# IC4KL_due_cont.net
KiCad netlist of a schematic drawn in EAGLE
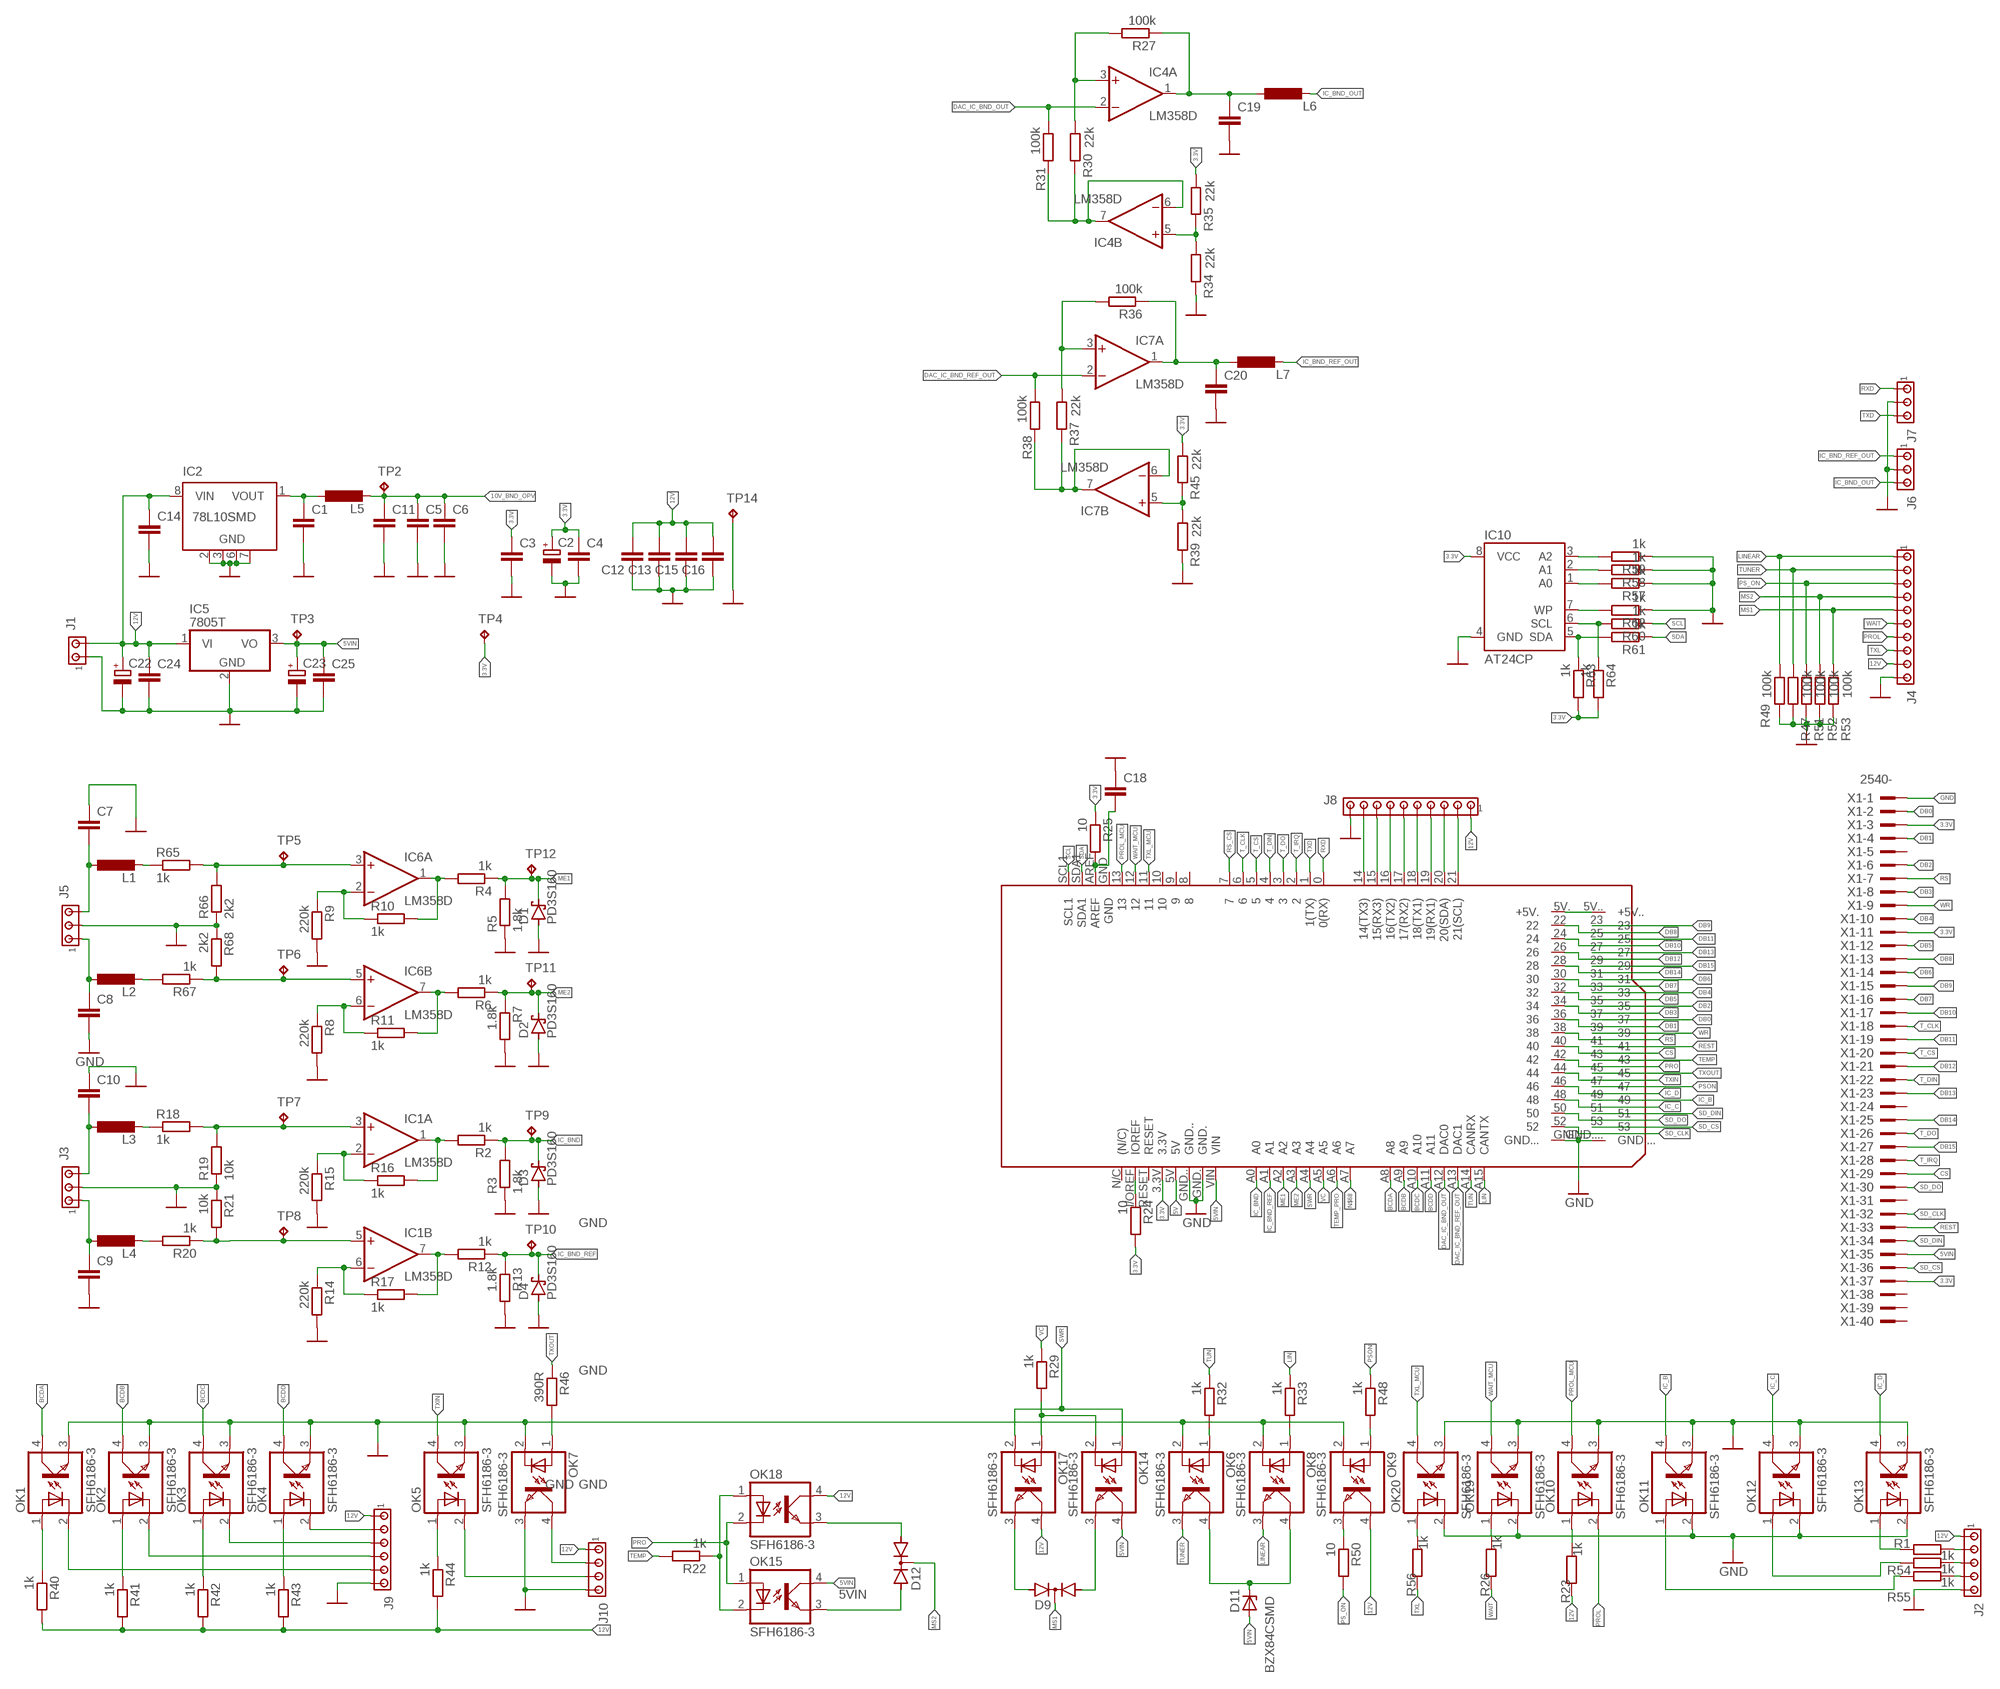
[diagram p0: schematic, sheet 1]

(export (version "E")
  (design (tool "Eeschema 10.0.6"))
  (components
    (comp (ref "C1")
      (value "1u")
      (footprint "eagle-import:C0805K")
      (libsource (lib "eagle-import") (part "C-EUC0805K"))
    )
    (comp (ref "C2")
      (value "CPOL-EU085CS-1AW")
      (footprint "eagle-import:085CS_1AW")
      (libsource (lib "eagle-import") (part "CPOL-EU085CS-1AW"))
    )
    (comp (ref "C3")
      (value "C-EUC0805K")
      (footprint "eagle-import:C0805K")
      (libsource (lib "eagle-import") (part "C-EUC0805K"))
    )
    (comp (ref "C4")
      (value "C-EUC0805K")
      (footprint "eagle-import:C0805K")
      (libsource (lib "eagle-import") (part "C-EUC0805K"))
    )
    (comp (ref "C5")
      (value "1u")
      (footprint "eagle-import:C0805K")
      (libsource (lib "eagle-import") (part "C-EUC0805K"))
    )
    (comp (ref "C6")
      (value "1u")
      (footprint "eagle-import:C0805K")
      (libsource (lib "eagle-import") (part "C-EUC0805K"))
    )
    (comp (ref "C7")
      (value "100n")
      (footprint "eagle-import:C0805K")
      (libsource (lib "eagle-import") (part "C-EUC0805K"))
    )
    (comp (ref "C8")
      (value "100n")
      (footprint "eagle-import:C0805K")
      (libsource (lib "eagle-import") (part "C-EUC0805K"))
    )
    (comp (ref "C9")
      (value "C-EUC0805K")
      (footprint "eagle-import:C0805K")
      (libsource (lib "eagle-import") (part "C-EUC0805K"))
    )
    (comp (ref "C10")
      (value "C-EUC0805K")
      (footprint "eagle-import:C0805K")
      (libsource (lib "eagle-import") (part "C-EUC0805K"))
    )
    (comp (ref "C11")
      (value "1u")
      (footprint "eagle-import:C0805K")
      (libsource (lib "eagle-import") (part "C-EUC0805K"))
    )
    (comp (ref "C12")
      (value "100n")
      (footprint "eagle-import:C0805K")
      (libsource (lib "eagle-import") (part "C-EUC0805K"))
    )
    (comp (ref "C13")
      (value "100n")
      (footprint "eagle-import:C0805K")
      (libsource (lib "eagle-import") (part "C-EUC0805K"))
    )
    (comp (ref "C14")
      (value "1u")
      (footprint "eagle-import:C0805K")
      (libsource (lib "eagle-import") (part "C-EUC0805K"))
    )
    (comp (ref "C15")
      (value "100n")
      (footprint "eagle-import:C0805K")
      (libsource (lib "eagle-import") (part "C-EUC0805K"))
    )
    (comp (ref "C16")
      (value "100n")
      (footprint "eagle-import:C0805K")
      (libsource (lib "eagle-import") (part "C-EUC0805K"))
    )
    (comp (ref "C18")
      (value "C-EUC0805K")
      (footprint "eagle-import:C0805K")
      (libsource (lib "eagle-import") (part "C-EUC0805K"))
    )
    (comp (ref "C19")
      (value "C-EUC0805K")
      (footprint "eagle-import:C0805K")
      (libsource (lib "eagle-import") (part "C-EUC0805K"))
    )
    (comp (ref "C20")
      (value "C-EUC0805K")
      (footprint "eagle-import:C0805K")
      (libsource (lib "eagle-import") (part "C-EUC0805K"))
    )
    (comp (ref "C22")
      (value "CPOL-EU150CLZ-1010")
      (footprint "eagle-import:150CLZ-1010")
      (libsource (lib "eagle-import") (part "CPOL-EU150CLZ-1010"))
    )
    (comp (ref "C23")
      (value "CPOL-EU150CLZ-1010")
      (footprint "eagle-import:150CLZ-1010")
      (libsource (lib "eagle-import") (part "CPOL-EU150CLZ-1010"))
    )
    (comp (ref "C24")
      (value "C-EUC0805K")
      (footprint "eagle-import:C0805K")
      (libsource (lib "eagle-import") (part "C-EUC0805K"))
    )
    (comp (ref "C25")
      (value "C-EUC0805K")
      (footprint "eagle-import:C0805K")
      (libsource (lib "eagle-import") (part "C-EUC0805K"))
    )
    (comp (ref "D1")
      (value "PD3S160")
      (footprint "eagle-import:POWERDI323")
      (libsource (lib "eagle-import") (part "PD3S160"))
    )
    (comp (ref "D2")
      (value "PD3S160")
      (footprint "eagle-import:POWERDI323")
      (libsource (lib "eagle-import") (part "PD3S160"))
    )
    (comp (ref "D3")
      (value "PD3S160")
      (footprint "eagle-import:POWERDI323")
      (libsource (lib "eagle-import") (part "PD3S160"))
    )
    (comp (ref "D4")
      (value "PD3S160")
      (footprint "eagle-import:POWERDI323")
      (libsource (lib "eagle-import") (part "PD3S160"))
    )
    (comp (ref "D9")
      (value "DIODE-2AC|CASOT23")
      (footprint "eagle-import:SOT23")
      (libsource (lib "eagle-import") (part "DIODE-2AC|CASOT23"))
    )
    (comp (ref "D11")
      (value "BZX84CSMD")
      (footprint "eagle-import:TO236")
      (libsource (lib "eagle-import") (part "BZX84CSMD"))
    )
    (comp (ref "D12")
      (value "DIODE-2AC|CASOT23")
      (footprint "eagle-import:SOT23")
      (libsource (lib "eagle-import") (part "DIODE-2AC|CASOT23"))
    )
    (comp (ref "IC1")
      (value "LM358D")
      (footprint "eagle-import:SO08")
      (libsource (lib "eagle-import") (part "LM358D"))
    )
    (comp (ref "IC2")
      (value "78L10SMD")
      (footprint "eagle-import:SO08")
      (libsource (lib "eagle-import") (part "78LSMD08"))
    )
    (comp (ref "IC4")
      (value "LM358D")
      (footprint "eagle-import:SO08")
      (libsource (lib "eagle-import") (part "linear_262_LM358D"))
    )
    (comp (ref "IC5")
      (value "7805T")
      (footprint "eagle-import:TO220H")
      (libsource (lib "eagle-import") (part "78T05"))
    )
    (comp (ref "IC6")
      (value "LM358D")
      (footprint "eagle-import:SO08")
      (libsource (lib "eagle-import") (part "LM358D"))
    )
    (comp (ref "IC7")
      (value "LM358D")
      (footprint "eagle-import:SO08")
      (libsource (lib "eagle-import") (part "linear_262_LM358D"))
    )
    (comp (ref "IC10")
      (value "AT24CP")
      (footprint "eagle-import:DIL08")
      (fields (field (name "MPN") "AT24C1024BW-SH-B"))
      (libsource (lib "eagle-import") (part "AT24CP"))
    )
    (comp (ref "J1")
      (value "MTA02-100")
      (footprint "eagle-import:10X02MTA")
      (libsource (lib "eagle-import") (part "MTA02-100"))
    )
    (comp (ref "J2")
      (value "MTA05-100")
      (footprint "eagle-import:10X05MTA")
      (libsource (lib "eagle-import") (part "MTA05-100"))
    )
    (comp (ref "J3")
      (value "MTA03-100")
      (footprint "eagle-import:10X03MTA")
      (libsource (lib "eagle-import") (part "MTA03-100"))
    )
    (comp (ref "J4")
      (value "MTA10-100")
      (footprint "eagle-import:10X10MTA")
      (libsource (lib "eagle-import") (part "MTA10-100"))
    )
    (comp (ref "J5")
      (value "MTA03-100")
      (footprint "eagle-import:10X03MTA")
      (libsource (lib "eagle-import") (part "MTA03-100"))
    )
    (comp (ref "J6")
      (value "MTA03-100")
      (footprint "eagle-import:10X03MTA")
      (libsource (lib "eagle-import") (part "MTA03-100"))
    )
    (comp (ref "J7")
      (value "MTA03-100")
      (footprint "eagle-import:10X03MTA")
      (libsource (lib "eagle-import") (part "MTA03-100"))
    )
    (comp (ref "J8")
      (value "MTA10-100")
      (footprint "eagle-import:10X10MTA")
      (libsource (lib "eagle-import") (part "MTA10-100"))
    )
    (comp (ref "J9")
      (value "MTA06-100")
      (footprint "eagle-import:10X06MTA")
      (libsource (lib "eagle-import") (part "MTA06-100"))
    )
    (comp (ref "J10")
      (value "MTA04-100")
      (footprint "eagle-import:10X04MTA")
      (libsource (lib "eagle-import") (part "MTA04-100"))
    )
    (comp (ref "L1")
      (value "L-EUL2012C")
      (footprint "eagle-import:L2012C")
      (libsource (lib "eagle-import") (part "L-EUL2012C"))
    )
    (comp (ref "L2")
      (value "L-EUL2012C")
      (footprint "eagle-import:L2012C")
      (libsource (lib "eagle-import") (part "L-EUL2012C"))
    )
    (comp (ref "L3")
      (value "L-EUL2012C")
      (footprint "eagle-import:L2012C")
      (libsource (lib "eagle-import") (part "L-EUL2012C"))
    )
    (comp (ref "L4")
      (value "L-EUL2012C")
      (footprint "eagle-import:L2012C")
      (libsource (lib "eagle-import") (part "L-EUL2012C"))
    )
    (comp (ref "L5")
      (value "L-EUL2012C")
      (footprint "eagle-import:L2012C")
      (libsource (lib "eagle-import") (part "L-EUL2012C"))
    )
    (comp (ref "L6")
      (value "L-EUL2012C")
      (footprint "eagle-import:L2012C")
      (libsource (lib "eagle-import") (part "L-EUL2012C"))
    )
    (comp (ref "L7")
      (value "L-EUL2012C")
      (footprint "eagle-import:L2012C")
      (libsource (lib "eagle-import") (part "L-EUL2012C"))
    )
    (comp (ref "OK1")
      (value "SFH6186-3")
      (footprint "eagle-import:SMD4")
      (fields (field (name "MF") "VISHAY/TELEFUNKEN"))
      (libsource (lib "eagle-import") (part "SFH618?6-3"))
    )
    (comp (ref "OK2")
      (value "SFH6186-3")
      (footprint "eagle-import:SMD4")
      (fields (field (name "MF") "VISHAY/TELEFUNKEN"))
      (libsource (lib "eagle-import") (part "SFH618?6-3"))
    )
    (comp (ref "OK3")
      (value "SFH6186-3")
      (footprint "eagle-import:SMD4")
      (fields (field (name "MF") "VISHAY/TELEFUNKEN"))
      (libsource (lib "eagle-import") (part "SFH618?6-3"))
    )
    (comp (ref "OK4")
      (value "SFH6186-3")
      (footprint "eagle-import:SMD4")
      (fields (field (name "MF") "VISHAY/TELEFUNKEN"))
      (libsource (lib "eagle-import") (part "SFH618?6-3"))
    )
    (comp (ref "OK5")
      (value "SFH6186-3")
      (footprint "eagle-import:SMD4")
      (fields (field (name "MF") "VISHAY/TELEFUNKEN"))
      (libsource (lib "eagle-import") (part "SFH618?6-3"))
    )
    (comp (ref "OK6")
      (value "SFH6186-3")
      (footprint "eagle-import:SMD4")
      (fields (field (name "MF") "VISHAY/TELEFUNKEN"))
      (libsource (lib "eagle-import") (part "SFH618?6-3"))
    )
    (comp (ref "OK7")
      (value "SFH6186-3")
      (footprint "eagle-import:SMD4")
      (fields (field (name "MF") "VISHAY/TELEFUNKEN"))
      (libsource (lib "eagle-import") (part "SFH618?6-3"))
    )
    (comp (ref "OK8")
      (value "SFH6186-3")
      (footprint "eagle-import:SMD4")
      (fields (field (name "MF") "VISHAY/TELEFUNKEN"))
      (libsource (lib "eagle-import") (part "SFH618?6-3"))
    )
    (comp (ref "OK9")
      (value "SFH6186-3")
      (footprint "eagle-import:SMD4")
      (fields (field (name "MF") "VISHAY/TELEFUNKEN"))
      (libsource (lib "eagle-import") (part "SFH618?6-3"))
    )
    (comp (ref "OK10")
      (value "SFH6186-3")
      (footprint "eagle-import:SMD4")
      (fields (field (name "MF") "VISHAY/TELEFUNKEN"))
      (libsource (lib "eagle-import") (part "SFH618?6-3"))
    )
    (comp (ref "OK11")
      (value "SFH6186-3")
      (footprint "eagle-import:SMD4")
      (fields (field (name "MF") "VISHAY/TELEFUNKEN"))
      (libsource (lib "eagle-import") (part "SFH618?6-3"))
    )
    (comp (ref "OK12")
      (value "SFH6186-3")
      (footprint "eagle-import:SMD4")
      (fields (field (name "MF") "VISHAY/TELEFUNKEN"))
      (libsource (lib "eagle-import") (part "SFH618?6-3"))
    )
    (comp (ref "OK13")
      (value "SFH6186-3")
      (footprint "eagle-import:SMD4")
      (fields (field (name "MF") "VISHAY/TELEFUNKEN"))
      (libsource (lib "eagle-import") (part "SFH618?6-3"))
    )
    (comp (ref "OK14")
      (value "SFH6186-3")
      (footprint "eagle-import:SMD4")
      (fields (field (name "MF") "VISHAY/TELEFUNKEN"))
      (libsource (lib "eagle-import") (part "SFH618?6-3"))
    )
    (comp (ref "OK15")
      (value "SFH6186-3")
      (footprint "eagle-import:SMD4")
      (fields (field (name "MF") "VISHAY/TELEFUNKEN"))
      (libsource (lib "eagle-import") (part "SFH618?6-3"))
    )
    (comp (ref "OK17")
      (value "SFH6186-3")
      (footprint "eagle-import:SMD4")
      (fields (field (name "MF") "VISHAY/TELEFUNKEN"))
      (libsource (lib "eagle-import") (part "SFH618?6-3"))
    )
    (comp (ref "OK18")
      (value "SFH6186-3")
      (footprint "eagle-import:SMD4")
      (fields (field (name "MF") "VISHAY/TELEFUNKEN"))
      (libsource (lib "eagle-import") (part "SFH618?6-3"))
    )
    (comp (ref "OK19")
      (value "SFH6186-3")
      (footprint "eagle-import:SMD4")
      (fields (field (name "MF") "VISHAY/TELEFUNKEN"))
      (libsource (lib "eagle-import") (part "SFH618?6-3"))
    )
    (comp (ref "OK20")
      (value "SFH6186-3")
      (footprint "eagle-import:SMD4")
      (fields (field (name "MF") "VISHAY/TELEFUNKEN"))
      (libsource (lib "eagle-import") (part "SFH618?6-3"))
    )
    (comp (ref "PCB1")
      (value "ARDUINO_DUE")
      (footprint "eagle-import:ARDUINO_DUE")
      (libsource (lib "eagle-import") (part "ARDUINO_DUE"))
    )
    (comp (ref "R1")
      (value "1k")
      (footprint "eagle-import:R0805")
      (libsource (lib "eagle-import") (part "R-EU_R0805"))
    )
    (comp (ref "R2")
      (value "1k")
      (footprint "eagle-import:R0805")
      (libsource (lib "eagle-import") (part "R-EU_R0805"))
    )
    (comp (ref "R3")
      (value "1.8k")
      (footprint "eagle-import:R0805")
      (libsource (lib "eagle-import") (part "R-EU_R0805"))
    )
    (comp (ref "R4")
      (value "1k")
      (footprint "eagle-import:R0805")
      (libsource (lib "eagle-import") (part "R-EU_R0805"))
    )
    (comp (ref "R5")
      (value "1.8k")
      (footprint "eagle-import:R0805")
      (libsource (lib "eagle-import") (part "R-EU_R0805"))
    )
    (comp (ref "R6")
      (value "1k")
      (footprint "eagle-import:R0805")
      (libsource (lib "eagle-import") (part "R-EU_R0805"))
    )
    (comp (ref "R7")
      (value "1.8k")
      (footprint "eagle-import:R0805")
      (libsource (lib "eagle-import") (part "R-EU_R0805"))
    )
    (comp (ref "R8")
      (value "220k")
      (footprint "eagle-import:R0805")
      (libsource (lib "eagle-import") (part "R-EU_R0805"))
    )
    (comp (ref "R9")
      (value "220k")
      (footprint "eagle-import:R0805")
      (libsource (lib "eagle-import") (part "R-EU_R0805"))
    )
    (comp (ref "R10")
      (value "1k")
      (footprint "eagle-import:R0805")
      (libsource (lib "eagle-import") (part "R-EU_R0805"))
    )
    (comp (ref "R11")
      (value "1k")
      (footprint "eagle-import:R0805")
      (libsource (lib "eagle-import") (part "R-EU_R0805"))
    )
    (comp (ref "R12")
      (value "1k")
      (footprint "eagle-import:R0805")
      (libsource (lib "eagle-import") (part "R-EU_R0805"))
    )
    (comp (ref "R13")
      (value "1.8k")
      (footprint "eagle-import:R0805")
      (libsource (lib "eagle-import") (part "R-EU_R0805"))
    )
    (comp (ref "R14")
      (value "220k")
      (footprint "eagle-import:R0805")
      (libsource (lib "eagle-import") (part "R-EU_R0805"))
    )
    (comp (ref "R15")
      (value "220k")
      (footprint "eagle-import:R0805")
      (libsource (lib "eagle-import") (part "R-EU_R0805"))
    )
    (comp (ref "R16")
      (value "1k")
      (footprint "eagle-import:R0805")
      (libsource (lib "eagle-import") (part "R-EU_R0805"))
    )
    (comp (ref "R17")
      (value "1k")
      (footprint "eagle-import:R0805")
      (libsource (lib "eagle-import") (part "R-EU_R0805"))
    )
    (comp (ref "R18")
      (value "1k")
      (footprint "eagle-import:R0805")
      (libsource (lib "eagle-import") (part "R-EU_R0805"))
    )
    (comp (ref "R19")
      (value "10k")
      (footprint "eagle-import:R0805")
      (libsource (lib "eagle-import") (part "R-EU_R0805"))
    )
    (comp (ref "R20")
      (value "1k")
      (footprint "eagle-import:R0805")
      (libsource (lib "eagle-import") (part "R-EU_R0805"))
    )
    (comp (ref "R21")
      (value "10k")
      (footprint "eagle-import:R0805")
      (libsource (lib "eagle-import") (part "R-EU_R0805"))
    )
    (comp (ref "R22")
      (value "1k")
      (footprint "eagle-import:R0805")
      (libsource (lib "eagle-import") (part "R-EU_R0805"))
    )
    (comp (ref "R23")
      (value "1k")
      (footprint "eagle-import:R0805")
      (libsource (lib "eagle-import") (part "R-EU_R0805"))
    )
    (comp (ref "R24")
      (value "10")
      (footprint "eagle-import:R0805")
      (libsource (lib "eagle-import") (part "R-EU_R0805"))
    )
    (comp (ref "R25")
      (value "10")
      (footprint "eagle-import:R0805")
      (libsource (lib "eagle-import") (part "R-EU_R0805"))
    )
    (comp (ref "R26")
      (value "1k")
      (footprint "eagle-import:R0805")
      (libsource (lib "eagle-import") (part "R-EU_R0805"))
    )
    (comp (ref "R27")
      (value "100k")
      (footprint "eagle-import:R0805")
      (libsource (lib "eagle-import") (part "R-EU_R0805"))
    )
    (comp (ref "R29")
      (value "1k")
      (footprint "eagle-import:R0805")
      (libsource (lib "eagle-import") (part "R-EU_R0805"))
    )
    (comp (ref "R30")
      (value "22k")
      (footprint "eagle-import:R0805")
      (libsource (lib "eagle-import") (part "R-EU_R0805"))
    )
    (comp (ref "R31")
      (value "100k")
      (footprint "eagle-import:R0805")
      (libsource (lib "eagle-import") (part "R-EU_R0805"))
    )
    (comp (ref "R32")
      (value "1k")
      (footprint "eagle-import:R0805")
      (libsource (lib "eagle-import") (part "R-EU_R0805"))
    )
    (comp (ref "R33")
      (value "1k")
      (footprint "eagle-import:R0805")
      (libsource (lib "eagle-import") (part "R-EU_R0805"))
    )
    (comp (ref "R34")
      (value "22k")
      (footprint "eagle-import:R0805")
      (libsource (lib "eagle-import") (part "R-EU_R0805"))
    )
    (comp (ref "R35")
      (value "22k")
      (footprint "eagle-import:R0805")
      (libsource (lib "eagle-import") (part "R-EU_R0805"))
    )
    (comp (ref "R36")
      (value "100k")
      (footprint "eagle-import:R0805")
      (libsource (lib "eagle-import") (part "R-EU_R0805"))
    )
    (comp (ref "R37")
      (value "22k")
      (footprint "eagle-import:R0805")
      (libsource (lib "eagle-import") (part "R-EU_R0805"))
    )
    (comp (ref "R38")
      (value "100k")
      (footprint "eagle-import:R0805")
      (libsource (lib "eagle-import") (part "R-EU_R0805"))
    )
    (comp (ref "R39")
      (value "22k")
      (footprint "eagle-import:R0805")
      (libsource (lib "eagle-import") (part "R-EU_R0805"))
    )
    (comp (ref "R40")
      (value "1k")
      (footprint "eagle-import:R0805")
      (libsource (lib "eagle-import") (part "R-EU_R0805"))
    )
    (comp (ref "R41")
      (value "1k")
      (footprint "eagle-import:R0805")
      (libsource (lib "eagle-import") (part "R-EU_R0805"))
    )
    (comp (ref "R42")
      (value "1k")
      (footprint "eagle-import:R0805")
      (libsource (lib "eagle-import") (part "R-EU_R0805"))
    )
    (comp (ref "R43")
      (value "1k")
      (footprint "eagle-import:R0805")
      (libsource (lib "eagle-import") (part "R-EU_R0805"))
    )
    (comp (ref "R44")
      (value "1k")
      (footprint "eagle-import:R0805")
      (libsource (lib "eagle-import") (part "R-EU_R0805"))
    )
    (comp (ref "R45")
      (value "22k")
      (footprint "eagle-import:R0805")
      (libsource (lib "eagle-import") (part "R-EU_R0805"))
    )
    (comp (ref "R46")
      (value "390R")
      (footprint "eagle-import:R0805")
      (libsource (lib "eagle-import") (part "R-EU_R0805"))
    )
    (comp (ref "R47")
      (value "100k")
      (footprint "eagle-import:R0805")
      (libsource (lib "eagle-import") (part "R-EU_R0805"))
    )
    (comp (ref "R48")
      (value "1k")
      (footprint "eagle-import:R0805")
      (libsource (lib "eagle-import") (part "R-EU_R0805"))
    )
    (comp (ref "R49")
      (value "100k")
      (footprint "eagle-import:R0805")
      (libsource (lib "eagle-import") (part "R-EU_R0805"))
    )
    (comp (ref "R50")
      (value "10")
      (footprint "eagle-import:R0805")
      (libsource (lib "eagle-import") (part "R-EU_R0805"))
    )
    (comp (ref "R51")
      (value "100k")
      (footprint "eagle-import:R0805")
      (libsource (lib "eagle-import") (part "R-EU_R0805"))
    )
    (comp (ref "R52")
      (value "100k")
      (footprint "eagle-import:R0805")
      (libsource (lib "eagle-import") (part "R-EU_R0805"))
    )
    (comp (ref "R53")
      (value "100k")
      (footprint "eagle-import:R0805")
      (libsource (lib "eagle-import") (part "R-EU_R0805"))
    )
    (comp (ref "R54")
      (value "1k")
      (footprint "eagle-import:R0805")
      (libsource (lib "eagle-import") (part "R-EU_R0805"))
    )
    (comp (ref "R55")
      (value "1k")
      (footprint "eagle-import:R0805")
      (libsource (lib "eagle-import") (part "R-EU_R0805"))
    )
    (comp (ref "R56")
      (value "1k")
      (footprint "eagle-import:R0805")
      (libsource (lib "eagle-import") (part "R-EU_R0805"))
    )
    (comp (ref "R57")
      (value "1k")
      (footprint "eagle-import:R0805")
      (libsource (lib "eagle-import") (part "R-EU_R0805"))
    )
    (comp (ref "R58")
      (value "1k")
      (footprint "eagle-import:R0805")
      (libsource (lib "eagle-import") (part "R-EU_R0805"))
    )
    (comp (ref "R59")
      (value "1k")
      (footprint "eagle-import:R0805")
      (libsource (lib "eagle-import") (part "R-EU_R0805"))
    )
    (comp (ref "R60")
      (value "1k")
      (footprint "eagle-import:R0805")
      (libsource (lib "eagle-import") (part "R-EU_R0805"))
    )
    (comp (ref "R61")
      (value "1k")
      (footprint "eagle-import:R0805")
      (libsource (lib "eagle-import") (part "R-EU_R0805"))
    )
    (comp (ref "R62")
      (value "1k")
      (footprint "eagle-import:R0805")
      (libsource (lib "eagle-import") (part "R-EU_R0805"))
    )
    (comp (ref "R63")
      (value "1k")
      (footprint "eagle-import:R0805")
      (libsource (lib "eagle-import") (part "R-EU_R0805"))
    )
    (comp (ref "R64")
      (value "1k")
      (footprint "eagle-import:R0805")
      (libsource (lib "eagle-import") (part "R-EU_R0805"))
    )
    (comp (ref "R65")
      (value "1k")
      (footprint "eagle-import:R0805")
      (libsource (lib "eagle-import") (part "R-EU_R0805"))
    )
    (comp (ref "R66")
      (value "2k2")
      (footprint "eagle-import:R0805")
      (libsource (lib "eagle-import") (part "R-EU_R0805"))
    )
    (comp (ref "R67")
      (value "1k")
      (footprint "eagle-import:R0805")
      (libsource (lib "eagle-import") (part "R-EU_R0805"))
    )
    (comp (ref "R68")
      (value "2k2")
      (footprint "eagle-import:R0805")
      (libsource (lib "eagle-import") (part "R-EU_R0805"))
    )
    (comp (ref "TP2")
      (value "TPB1,27")
      (footprint "eagle-import:B1,27")
      (libsource (lib "eagle-import") (part "TPB1,27"))
    )
    (comp (ref "TP3")
      (value "TPB1,27")
      (footprint "eagle-import:B1,27")
      (libsource (lib "eagle-import") (part "TPB1,27"))
    )
    (comp (ref "TP4")
      (value "TPB1,27")
      (footprint "eagle-import:B1,27")
      (libsource (lib "eagle-import") (part "TPB1,27"))
    )
    (comp (ref "TP5")
      (value "TPB1,27")
      (footprint "eagle-import:B1,27")
      (libsource (lib "eagle-import") (part "TPB1,27"))
    )
    (comp (ref "TP6")
      (value "TPB1,27")
      (footprint "eagle-import:B1,27")
      (libsource (lib "eagle-import") (part "TPB1,27"))
    )
    (comp (ref "TP7")
      (value "TPB1,27")
      (footprint "eagle-import:B1,27")
      (libsource (lib "eagle-import") (part "TPB1,27"))
    )
    (comp (ref "TP8")
      (value "TPB1,27")
      (footprint "eagle-import:B1,27")
      (libsource (lib "eagle-import") (part "TPB1,27"))
    )
    (comp (ref "TP9")
      (value "TPB1,27")
      (footprint "eagle-import:B1,27")
      (libsource (lib "eagle-import") (part "TPB1,27"))
    )
    (comp (ref "TP10")
      (value "TPB1,27")
      (footprint "eagle-import:B1,27")
      (libsource (lib "eagle-import") (part "TPB1,27"))
    )
    (comp (ref "TP11")
      (value "TPB1,27")
      (footprint "eagle-import:B1,27")
      (libsource (lib "eagle-import") (part "TPB1,27"))
    )
    (comp (ref "TP12")
      (value "TPB1,27")
      (footprint "eagle-import:B1,27")
      (libsource (lib "eagle-import") (part "TPB1,27"))
    )
    (comp (ref "TP14")
      (value "TPB1,27")
      (footprint "eagle-import:B1,27")
      (libsource (lib "eagle-import") (part "TPB1,27"))
    )
    (comp (ref "X1")
      (value "2540-")
      (footprint "eagle-import:PAK100_2500-40")
      (libsource (lib "eagle-import") (part "2540-"))
    )
  )
  (nets
    (net (code "1") (name "3.3V") (class "Default")
      (node (ref "C2") (pin "+") (pinfunction "+_+") (pintype "passive"))
      (node (ref "C3") (pin "1") (pinfunction "1_1") (pintype "passive"))
      (node (ref "C4") (pin "1") (pinfunction "1_1") (pintype "passive"))
      (node (ref "IC10") (pin "8") (pinfunction "VCC_8") (pintype "power_in"))
      (node (ref "PCB1") (pin "3.3V") (pinfunction "3.3V_3.3V") (pintype "bidirectional"))
      (node (ref "R24") (pin "2") (pinfunction "2_2") (pintype "passive"))
      (node (ref "R25") (pin "1") (pinfunction "1_1") (pintype "passive"))
      (node (ref "R35") (pin "1") (pinfunction "1_1") (pintype "passive"))
      (node (ref "R45") (pin "1") (pinfunction "1_1") (pintype "passive"))
      (node (ref "R63") (pin "2") (pinfunction "2_2") (pintype "passive"))
      (node (ref "R64") (pin "2") (pinfunction "2_2") (pintype "passive"))
      (node (ref "TP4") (pin "TP") (pinfunction "TP_TP") (pintype "input"))
      (node (ref "X1") (pin "11") (pinfunction "KL_11") (pintype "passive"))
      (node (ref "X1") (pin "3") (pinfunction "KL_3") (pintype "passive"))
      (node (ref "X1") (pin "37") (pinfunction "KL_37") (pintype "passive"))
    )
    (net (code "2") (name "5V") (class "Default")
      (node (ref "PCB1") (pin "5V") (pinfunction "5V_5V") (pintype "bidirectional"))
    )
    (net (code "3") (name "5VIN") (class "Default")
      (node (ref "C23") (pin "+") (pinfunction "+_+") (pintype "passive"))
      (node (ref "C25") (pin "1") (pinfunction "1_1") (pintype "passive"))
      (node (ref "D11") (pin "A") (pinfunction "A_A") (pintype "passive"))
      (node (ref "IC5") (pin "3") (pinfunction "VO_3") (pintype "passive"))
      (node (ref "OK14") (pin "4") (pinfunction "COL_4") (pintype "passive"))
      (node (ref "OK15") (pin "4") (pinfunction "COL_4") (pintype "passive"))
      (node (ref "PCB1") (pin "VIN") (pinfunction "VIN_VIN") (pintype "bidirectional"))
      (node (ref "TP3") (pin "TP") (pinfunction "TP_TP") (pintype "input"))
      (node (ref "X1") (pin "35") (pinfunction "KL_35") (pintype "passive"))
    )
    (net (code "4") (name "10V_BND_OPV") (class "Default")
      (node (ref "C11") (pin "1") (pinfunction "1_1") (pintype "passive"))
      (node (ref "C5") (pin "1") (pinfunction "1_1") (pintype "passive"))
      (node (ref "C6") (pin "1") (pinfunction "1_1") (pintype "passive"))
      (node (ref "L5") (pin "2") (pinfunction "2_2") (pintype "passive"))
      (node (ref "TP2") (pin "TP") (pinfunction "TP_TP") (pintype "input"))
    )
    (net (code "5") (name "12V") (class "Default")
      (node (ref "C12") (pin "2") (pinfunction "2_2") (pintype "passive"))
      (node (ref "C13") (pin "2") (pinfunction "2_2") (pintype "passive"))
      (node (ref "C14") (pin "1") (pinfunction "1_1") (pintype "passive"))
      (node (ref "C15") (pin "2") (pinfunction "2_2") (pintype "passive"))
      (node (ref "C16") (pin "2") (pinfunction "2_2") (pintype "passive"))
      (node (ref "C22") (pin "+") (pinfunction "+_+") (pintype "passive"))
      (node (ref "C24") (pin "1") (pinfunction "1_1") (pintype "passive"))
      (node (ref "IC2") (pin "8") (pinfunction "VIN_8") (pintype "passive"))
      (node (ref "IC5") (pin "1") (pinfunction "VI_1") (pintype "input"))
      (node (ref "J1") (pin "2") (pinfunction "2_2") (pintype "passive"))
      (node (ref "J10") (pin "1") (pinfunction "1_1") (pintype "passive"))
      (node (ref "J2") (pin "1") (pinfunction "1_1") (pintype "passive"))
      (node (ref "J4") (pin "9") (pinfunction "9_9") (pintype "passive"))
      (node (ref "J8") (pin "1") (pinfunction "1_1") (pintype "passive"))
      (node (ref "J9") (pin "6") (pinfunction "1_6") (pintype "passive"))
      (node (ref "OK17") (pin "4") (pinfunction "COL_4") (pintype "passive"))
      (node (ref "OK18") (pin "4") (pinfunction "COL_4") (pintype "passive"))
      (node (ref "OK9") (pin "4") (pinfunction "COL_4") (pintype "passive"))
      (node (ref "R23") (pin "1") (pinfunction "1_1") (pintype "passive"))
      (node (ref "R40") (pin "2") (pinfunction "2_2") (pintype "passive"))
      (node (ref "R41") (pin "2") (pinfunction "2_2") (pintype "passive"))
      (node (ref "R42") (pin "2") (pinfunction "2_2") (pintype "passive"))
      (node (ref "R43") (pin "2") (pinfunction "2_2") (pintype "passive"))
      (node (ref "R44") (pin "2") (pinfunction "2_2") (pintype "passive"))
    )
    (net (code "6") (name "BCDA") (class "Default")
      (node (ref "OK1") (pin "4") (pinfunction "COL_4") (pintype "passive"))
      (node (ref "PCB1") (pin "A8") (pinfunction "A8_A8") (pintype "bidirectional"))
    )
    (net (code "7") (name "BCDB") (class "Default")
      (node (ref "OK2") (pin "4") (pinfunction "COL_4") (pintype "passive"))
      (node (ref "PCB1") (pin "A9") (pinfunction "A9_A9") (pintype "bidirectional"))
    )
    (net (code "8") (name "BCDC") (class "Default")
      (node (ref "OK3") (pin "4") (pinfunction "COL_4") (pintype "passive"))
      (node (ref "PCB1") (pin "A10") (pinfunction "A10_A10") (pintype "bidirectional"))
    )
    (net (code "9") (name "BCDD") (class "Default")
      (node (ref "OK4") (pin "4") (pinfunction "COL_4") (pintype "passive"))
      (node (ref "PCB1") (pin "A11") (pinfunction "A11_A11") (pintype "bidirectional"))
    )
    (net (code "10") (name "CS") (class "Default")
      (node (ref "PCB1") (pin "40") (pinfunction "40_40") (pintype "bidirectional"))
      (node (ref "X1") (pin "29") (pinfunction "KL_29") (pintype "passive"))
    )
    (net (code "11") (name "DAC_IC_BND_OUT") (class "Default")
      (node (ref "IC4") (pin "2") (pinfunction "-IN_2") (pintype "input"))
      (node (ref "PCB1") (pin "A12") (pinfunction "DAC0_A12") (pintype "bidirectional"))
      (node (ref "R31") (pin "1") (pinfunction "1_1") (pintype "passive"))
    )
    (net (code "12") (name "DAC_IC_BND_REF_OUT") (class "Default")
      (node (ref "IC7") (pin "2") (pinfunction "-IN_2") (pintype "input"))
      (node (ref "PCB1") (pin "A13") (pinfunction "DAC1_A13") (pintype "bidirectional"))
      (node (ref "R38") (pin "1") (pinfunction "1_1") (pintype "passive"))
    )
    (net (code "13") (name "DB0") (class "Default")
      (node (ref "PCB1") (pin "37") (pinfunction "37_37") (pintype "bidirectional"))
      (node (ref "X1") (pin "2") (pinfunction "KL_2") (pintype "passive"))
    )
    (net (code "14") (name "DB1") (class "Default")
      (node (ref "PCB1") (pin "36") (pinfunction "36_36") (pintype "bidirectional"))
      (node (ref "X1") (pin "4") (pinfunction "KL_4") (pintype "passive"))
    )
    (net (code "15") (name "DB2") (class "Default")
      (node (ref "PCB1") (pin "35") (pinfunction "35_35") (pintype "bidirectional"))
      (node (ref "X1") (pin "6") (pinfunction "KL_6") (pintype "passive"))
    )
    (net (code "16") (name "DB3") (class "Default")
      (node (ref "PCB1") (pin "34") (pinfunction "34_34") (pintype "bidirectional"))
      (node (ref "X1") (pin "8") (pinfunction "KL_8") (pintype "passive"))
    )
    (net (code "17") (name "DB4") (class "Default")
      (node (ref "PCB1") (pin "33") (pinfunction "33_33") (pintype "bidirectional"))
      (node (ref "X1") (pin "10") (pinfunction "KL_10") (pintype "passive"))
    )
    (net (code "18") (name "DB5") (class "Default")
      (node (ref "PCB1") (pin "32") (pinfunction "32_32") (pintype "bidirectional"))
      (node (ref "X1") (pin "12") (pinfunction "KL_12") (pintype "passive"))
    )
    (net (code "19") (name "DB6") (class "Default")
      (node (ref "PCB1") (pin "31") (pinfunction "31_31") (pintype "bidirectional"))
      (node (ref "X1") (pin "14") (pinfunction "KL_14") (pintype "passive"))
    )
    (net (code "20") (name "DB7") (class "Default")
      (node (ref "PCB1") (pin "30") (pinfunction "30_30") (pintype "bidirectional"))
      (node (ref "X1") (pin "16") (pinfunction "KL_16") (pintype "passive"))
    )
    (net (code "21") (name "DB8") (class "Default")
      (node (ref "PCB1") (pin "22") (pinfunction "22_22") (pintype "bidirectional"))
      (node (ref "X1") (pin "13") (pinfunction "KL_13") (pintype "passive"))
    )
    (net (code "22") (name "DB9") (class "Default")
      (node (ref "PCB1") (pin "23") (pinfunction "23_23") (pintype "bidirectional"))
      (node (ref "X1") (pin "15") (pinfunction "KL_15") (pintype "passive"))
    )
    (net (code "23") (name "DB10") (class "Default")
      (node (ref "PCB1") (pin "24") (pinfunction "24_24") (pintype "bidirectional"))
      (node (ref "X1") (pin "17") (pinfunction "KL_17") (pintype "passive"))
    )
    (net (code "24") (name "DB11") (class "Default")
      (node (ref "PCB1") (pin "25") (pinfunction "25_25") (pintype "bidirectional"))
      (node (ref "X1") (pin "19") (pinfunction "KL_19") (pintype "passive"))
    )
    (net (code "25") (name "DB12") (class "Default")
      (node (ref "PCB1") (pin "26") (pinfunction "26_26") (pintype "bidirectional"))
      (node (ref "X1") (pin "21") (pinfunction "KL_21") (pintype "passive"))
    )
    (net (code "26") (name "DB13") (class "Default")
      (node (ref "PCB1") (pin "27") (pinfunction "27_27") (pintype "bidirectional"))
      (node (ref "X1") (pin "23") (pinfunction "KL_23") (pintype "passive"))
    )
    (net (code "27") (name "DB14") (class "Default")
      (node (ref "PCB1") (pin "28") (pinfunction "28_28") (pintype "bidirectional"))
      (node (ref "X1") (pin "25") (pinfunction "KL_25") (pintype "passive"))
    )
    (net (code "28") (name "DB15") (class "Default")
      (node (ref "PCB1") (pin "29") (pinfunction "29_29") (pintype "bidirectional"))
      (node (ref "X1") (pin "27") (pinfunction "KL_27") (pintype "passive"))
    )
    (net (code "29") (name "GND") (class "Default")
      (node (ref "C1") (pin "2") (pinfunction "2_2") (pintype "passive"))
      (node (ref "C10") (pin "1") (pinfunction "1_1") (pintype "passive"))
      (node (ref "C11") (pin "2") (pinfunction "2_2") (pintype "passive"))
      (node (ref "C12") (pin "1") (pinfunction "1_1") (pintype "passive"))
      (node (ref "C13") (pin "1") (pinfunction "1_1") (pintype "passive"))
      (node (ref "C14") (pin "2") (pinfunction "2_2") (pintype "passive"))
      (node (ref "C15") (pin "1") (pinfunction "1_1") (pintype "passive"))
      (node (ref "C16") (pin "1") (pinfunction "1_1") (pintype "passive"))
      (node (ref "C18") (pin "1") (pinfunction "1_1") (pintype "passive"))
      (node (ref "C19") (pin "2") (pinfunction "2_2") (pintype "passive"))
      (node (ref "C2") (pin "-") (pinfunction "-_-") (pintype "passive"))
      (node (ref "C20") (pin "2") (pinfunction "2_2") (pintype "passive"))
      (node (ref "C22") (pin "-") (pinfunction "-_-") (pintype "passive"))
      (node (ref "C23") (pin "-") (pinfunction "-_-") (pintype "passive"))
      (node (ref "C24") (pin "2") (pinfunction "2_2") (pintype "passive"))
      (node (ref "C25") (pin "2") (pinfunction "2_2") (pintype "passive"))
      (node (ref "C3") (pin "2") (pinfunction "2_2") (pintype "passive"))
      (node (ref "C4") (pin "2") (pinfunction "2_2") (pintype "passive"))
      (node (ref "C5") (pin "2") (pinfunction "2_2") (pintype "passive"))
      (node (ref "C6") (pin "2") (pinfunction "2_2") (pintype "passive"))
      (node (ref "C7") (pin "1") (pinfunction "1_1") (pintype "passive"))
      (node (ref "C8") (pin "2") (pinfunction "2_2") (pintype "passive"))
      (node (ref "C9") (pin "2") (pinfunction "2_2") (pintype "passive"))
      (node (ref "D1") (pin "A") (pinfunction "A_A") (pintype "passive"))
      (node (ref "D2") (pin "A") (pinfunction "A_A") (pintype "passive"))
      (node (ref "D3") (pin "A") (pinfunction "A_A") (pintype "passive"))
      (node (ref "D4") (pin "A") (pinfunction "A_A") (pintype "passive"))
      (node (ref "IC10") (pin "4") (pinfunction "GND_4") (pintype "power_in"))
      (node (ref "IC2") (pin "2") (pinfunction "GND_2") (pintype "power_in"))
      (node (ref "IC2") (pin "3") (pinfunction "GND_3") (pintype "power_in"))
      (node (ref "IC2") (pin "6") (pinfunction "GND_6") (pintype "power_in"))
      (node (ref "IC2") (pin "7") (pinfunction "GND_7") (pintype "power_in"))
      (node (ref "IC5") (pin "2") (pinfunction "GND_2") (pintype "passive"))
      (node (ref "J1") (pin "1") (pinfunction "1_1") (pintype "passive"))
      (node (ref "J10") (pin "4") (pinfunction "4_4") (pintype "passive"))
      (node (ref "J2") (pin "5") (pinfunction "5_5") (pintype "passive"))
      (node (ref "J3") (pin "2") (pinfunction "2_2") (pintype "passive"))
      (node (ref "J4") (pin "10") (pinfunction "10_10") (pintype "passive"))
      (node (ref "J5") (pin "2") (pinfunction "2_2") (pintype "passive"))
      (node (ref "J6") (pin "2") (pinfunction "2_2") (pintype "passive"))
      (node (ref "J7") (pin "2") (pinfunction "2_2") (pintype "passive"))
      (node (ref "J8") (pin "10") (pinfunction "10_10") (pintype "passive"))
      (node (ref "J9") (pin "1") (pinfunction "6_1") (pintype "passive"))
      (node (ref "OK1") (pin "3") (pinfunction "EMIT_3") (pintype "passive"))
      (node (ref "OK10") (pin "3") (pinfunction "EMIT_3") (pintype "passive"))
      (node (ref "OK11") (pin "2") (pinfunction "C_2") (pintype "passive"))
      (node (ref "OK11") (pin "3") (pinfunction "EMIT_3") (pintype "passive"))
      (node (ref "OK12") (pin "2") (pinfunction "C_2") (pintype "passive"))
      (node (ref "OK12") (pin "3") (pinfunction "EMIT_3") (pintype "passive"))
      (node (ref "OK13") (pin "2") (pinfunction "C_2") (pintype "passive"))
      (node (ref "OK13") (pin "3") (pinfunction "EMIT_3") (pintype "passive"))
      (node (ref "OK19") (pin "2") (pinfunction "C_2") (pintype "passive"))
      (node (ref "OK19") (pin "3") (pinfunction "EMIT_3") (pintype "passive"))
      (node (ref "OK2") (pin "3") (pinfunction "EMIT_3") (pintype "passive"))
      (node (ref "OK20") (pin "2") (pinfunction "C_2") (pintype "passive"))
      (node (ref "OK20") (pin "3") (pinfunction "EMIT_3") (pintype "passive"))
      (node (ref "OK3") (pin "3") (pinfunction "EMIT_3") (pintype "passive"))
      (node (ref "OK4") (pin "3") (pinfunction "EMIT_3") (pintype "passive"))
      (node (ref "OK5") (pin "3") (pinfunction "EMIT_3") (pintype "passive"))
      (node (ref "OK6") (pin "2") (pinfunction "C_2") (pintype "passive"))
      (node (ref "OK7") (pin "2") (pinfunction "C_2") (pintype "passive"))
      (node (ref "OK7") (pin "3") (pinfunction "EMIT_3") (pintype "passive"))
      (node (ref "OK8") (pin "2") (pinfunction "C_2") (pintype "passive"))
      (node (ref "OK9") (pin "2") (pinfunction "C_2") (pintype "passive"))
      (node (ref "PCB1") (pin "GND.") (pinfunction "GND._GND.") (pintype "bidirectional"))
      (node (ref "PCB1") (pin "GND..") (pinfunction "GND.._GND..") (pintype "bidirectional"))
      (node (ref "PCB1") (pin "GND...") (pinfunction "GND..._GND...") (pintype "bidirectional"))
      (node (ref "PCB1") (pin "GND....") (pinfunction "GND...._GND....") (pintype "bidirectional"))
      (node (ref "R13") (pin "2") (pinfunction "2_2") (pintype "passive"))
      (node (ref "R14") (pin "2") (pinfunction "2_2") (pintype "passive"))
      (node (ref "R15") (pin "2") (pinfunction "2_2") (pintype "passive"))
      (node (ref "R19") (pin "1") (pinfunction "1_1") (pintype "passive"))
      (node (ref "R21") (pin "1") (pinfunction "1_1") (pintype "passive"))
      (node (ref "R3") (pin "1") (pinfunction "1_1") (pintype "passive"))
      (node (ref "R34") (pin "2") (pinfunction "2_2") (pintype "passive"))
      (node (ref "R39") (pin "2") (pinfunction "2_2") (pintype "passive"))
      (node (ref "R47") (pin "2") (pinfunction "2_2") (pintype "passive"))
      (node (ref "R49") (pin "2") (pinfunction "2_2") (pintype "passive"))
      (node (ref "R5") (pin "1") (pinfunction "1_1") (pintype "passive"))
      (node (ref "R51") (pin "2") (pinfunction "2_2") (pintype "passive"))
      (node (ref "R52") (pin "2") (pinfunction "2_2") (pintype "passive"))
      (node (ref "R53") (pin "2") (pinfunction "2_2") (pintype "passive"))
      (node (ref "R57") (pin "1") (pinfunction "1_1") (pintype "passive"))
      (node (ref "R58") (pin "1") (pinfunction "1_1") (pintype "passive"))
      (node (ref "R59") (pin "1") (pinfunction "1_1") (pintype "passive"))
      (node (ref "R62") (pin "1") (pinfunction "1_1") (pintype "passive"))
      (node (ref "R66") (pin "1") (pinfunction "1_1") (pintype "passive"))
      (node (ref "R68") (pin "1") (pinfunction "1_1") (pintype "passive"))
      (node (ref "R7") (pin "2") (pinfunction "2_2") (pintype "passive"))
      (node (ref "R8") (pin "2") (pinfunction "2_2") (pintype "passive"))
      (node (ref "R9") (pin "2") (pinfunction "2_2") (pintype "passive"))
      (node (ref "TP14") (pin "TP") (pinfunction "TP_TP") (pintype "input"))
      (node (ref "X1") (pin "1") (pinfunction "KL_1") (pintype "passive"))
    )
    (net (code "30") (name "IC_B") (class "Default")
      (node (ref "OK11") (pin "4") (pinfunction "COL_4") (pintype "passive"))
      (node (ref "PCB1") (pin "49") (pinfunction "49_49") (pintype "bidirectional"))
    )
    (net (code "31") (name "IC_BND") (class "Default")
      (node (ref "D3") (pin "C") (pinfunction "C_C") (pintype "passive"))
      (node (ref "PCB1") (pin "A0") (pinfunction "A0_A0") (pintype "bidirectional"))
      (node (ref "R2") (pin "1") (pinfunction "1_1") (pintype "passive"))
      (node (ref "R3") (pin "2") (pinfunction "2_2") (pintype "passive"))
      (node (ref "TP9") (pin "TP") (pinfunction "TP_TP") (pintype "input"))
    )
    (net (code "32") (name "IC_BND_OUT") (class "Default")
      (node (ref "J6") (pin "3") (pinfunction "3_3") (pintype "passive"))
      (node (ref "L6") (pin "2") (pinfunction "2_2") (pintype "passive"))
    )
    (net (code "33") (name "IC_BND_REF") (class "Default")
      (node (ref "D4") (pin "C") (pinfunction "C_C") (pintype "passive"))
      (node (ref "PCB1") (pin "A1") (pinfunction "A1_A1") (pintype "bidirectional"))
      (node (ref "R12") (pin "1") (pinfunction "1_1") (pintype "passive"))
      (node (ref "R13") (pin "1") (pinfunction "1_1") (pintype "passive"))
      (node (ref "TP10") (pin "TP") (pinfunction "TP_TP") (pintype "input"))
    )
    (net (code "34") (name "IC_BND_REF_OUT") (class "Default")
      (node (ref "J6") (pin "1") (pinfunction "1_1") (pintype "passive"))
      (node (ref "L7") (pin "2") (pinfunction "2_2") (pintype "passive"))
    )
    (net (code "35") (name "IC_C") (class "Default")
      (node (ref "OK12") (pin "4") (pinfunction "COL_4") (pintype "passive"))
      (node (ref "PCB1") (pin "48") (pinfunction "48_48") (pintype "bidirectional"))
    )
    (net (code "36") (name "IC_D") (class "Default")
      (node (ref "OK13") (pin "4") (pinfunction "COL_4") (pintype "passive"))
      (node (ref "PCB1") (pin "46") (pinfunction "46_46") (pintype "bidirectional"))
    )
    (net (code "37") (name "LIN") (class "Default")
      (node (ref "PCB1") (pin "A15") (pinfunction "CANTX_A15") (pintype "bidirectional"))
      (node (ref "R33") (pin "1") (pinfunction "1_1") (pintype "passive"))
    )
    (net (code "38") (name "LINEAR") (class "Default")
      (node (ref "J4") (pin "1") (pinfunction "1_1") (pintype "passive"))
      (node (ref "OK8") (pin "3") (pinfunction "EMIT_3") (pintype "passive"))
      (node (ref "R49") (pin "1") (pinfunction "1_1") (pintype "passive"))
    )
    (net (code "39") (name "ME1") (class "Default")
      (node (ref "D1") (pin "C") (pinfunction "C_C") (pintype "passive"))
      (node (ref "PCB1") (pin "A2") (pinfunction "A2_A2") (pintype "bidirectional"))
      (node (ref "R4") (pin "1") (pinfunction "1_1") (pintype "passive"))
      (node (ref "R5") (pin "2") (pinfunction "2_2") (pintype "passive"))
      (node (ref "TP12") (pin "TP") (pinfunction "TP_TP") (pintype "input"))
    )
    (net (code "40") (name "ME2") (class "Default")
      (node (ref "D2") (pin "C") (pinfunction "C_C") (pintype "passive"))
      (node (ref "PCB1") (pin "A3") (pinfunction "A3_A3") (pintype "bidirectional"))
      (node (ref "R6") (pin "1") (pinfunction "1_1") (pintype "passive"))
      (node (ref "R7") (pin "1") (pinfunction "1_1") (pintype "passive"))
      (node (ref "TP11") (pin "TP") (pinfunction "TP_TP") (pintype "input"))
    )
    (net (code "41") (name "MS1") (class "Default")
      (node (ref "D9") (pin "3") (pinfunction "C_3") (pintype "passive"))
      (node (ref "J4") (pin "5") (pinfunction "5_5") (pintype "passive"))
      (node (ref "R53") (pin "1") (pinfunction "1_1") (pintype "passive"))
    )
    (net (code "42") (name "MS2") (class "Default")
      (node (ref "D12") (pin "3") (pinfunction "C_3") (pintype "passive"))
      (node (ref "J4") (pin "4") (pinfunction "4_4") (pintype "passive"))
      (node (ref "R52") (pin "1") (pinfunction "1_1") (pintype "passive"))
    )
    (net (code "43") (name "N$68") (class "Default")
      (node (ref "PCB1") (pin "A7") (pinfunction "A7_A7") (pintype "bidirectional"))
    )
    (net (code "44") (name "Net-(C7-Pad2)") (class "Default")
      (node (ref "C7") (pin "2") (pinfunction "2_2") (pintype "passive"))
      (node (ref "J5") (pin "3") (pinfunction "3_3") (pintype "passive"))
      (node (ref "L1") (pin "1") (pinfunction "1_1") (pintype "passive"))
    )
    (net (code "45") (name "Net-(C8-Pad1)") (class "Default")
      (node (ref "C8") (pin "1") (pinfunction "1_1") (pintype "passive"))
      (node (ref "J5") (pin "1") (pinfunction "1_1") (pintype "passive"))
      (node (ref "L2") (pin "1") (pinfunction "1_1") (pintype "passive"))
    )
    (net (code "46") (name "Net-(C9-Pad1)") (class "Default")
      (node (ref "C9") (pin "1") (pinfunction "1_1") (pintype "passive"))
      (node (ref "J3") (pin "1") (pinfunction "1_1") (pintype "passive"))
      (node (ref "L4") (pin "1") (pinfunction "1_1") (pintype "passive"))
    )
    (net (code "47") (name "Net-(C10-Pad2)") (class "Default")
      (node (ref "C10") (pin "2") (pinfunction "2_2") (pintype "passive"))
      (node (ref "J3") (pin "3") (pinfunction "3_3") (pintype "passive"))
      (node (ref "L3") (pin "1") (pinfunction "1_1") (pintype "passive"))
    )
    (net (code "48") (name "Net-(C18-Pad2)") (class "Default")
      (node (ref "C18") (pin "2") (pinfunction "2_2") (pintype "passive"))
      (node (ref "PCB1") (pin "AREF") (pinfunction "AREF_AREF") (pintype "bidirectional"))
      (node (ref "R25") (pin "2") (pinfunction "2_2") (pintype "passive"))
    )
    (net (code "49") (name "Net-(D9-A1)") (class "Default")
      (node (ref "D9") (pin "1") (pinfunction "A1_1") (pintype "passive"))
      (node (ref "OK14") (pin "3") (pinfunction "EMIT_3") (pintype "passive"))
    )
    (net (code "50") (name "Net-(D9-A2)") (class "Default")
      (node (ref "D9") (pin "2") (pinfunction "A2_2") (pintype "passive"))
      (node (ref "OK17") (pin "3") (pinfunction "EMIT_3") (pintype "passive"))
    )
    (net (code "51") (name "Net-(D12-A1)") (class "Default")
      (node (ref "D12") (pin "1") (pinfunction "A1_1") (pintype "passive"))
      (node (ref "OK18") (pin "3") (pinfunction "EMIT_3") (pintype "passive"))
    )
    (net (code "52") (name "Net-(D12-A2)") (class "Default")
      (node (ref "D12") (pin "2") (pinfunction "A2_2") (pintype "passive"))
      (node (ref "OK15") (pin "3") (pinfunction "EMIT_3") (pintype "passive"))
    )
    (net (code "53") (name "Net-(IC1A-+IN)") (class "Default")
      (node (ref "IC1") (pin "3") (pinfunction "+IN_3") (pintype "input"))
      (node (ref "R18") (pin "2") (pinfunction "2_2") (pintype "passive"))
      (node (ref "R19") (pin "2") (pinfunction "2_2") (pintype "passive"))
      (node (ref "TP7") (pin "TP") (pinfunction "TP_TP") (pintype "input"))
    )
    (net (code "54") (name "Net-(IC1A--IN)") (class "Default")
      (node (ref "IC1") (pin "2") (pinfunction "-IN_2") (pintype "input"))
      (node (ref "R15") (pin "1") (pinfunction "1_1") (pintype "passive"))
      (node (ref "R16") (pin "1") (pinfunction "1_1") (pintype "passive"))
    )
    (net (code "55") (name "Net-(IC1A-OUT)") (class "Default")
      (node (ref "IC1") (pin "1") (pinfunction "OUT_1") (pintype "output"))
      (node (ref "R16") (pin "2") (pinfunction "2_2") (pintype "passive"))
      (node (ref "R2") (pin "2") (pinfunction "2_2") (pintype "passive"))
    )
    (net (code "56") (name "Net-(IC1B-+IN)") (class "Default")
      (node (ref "IC1") (pin "5") (pinfunction "+IN_5") (pintype "input"))
      (node (ref "R20") (pin "1") (pinfunction "1_1") (pintype "passive"))
      (node (ref "R21") (pin "2") (pinfunction "2_2") (pintype "passive"))
      (node (ref "TP8") (pin "TP") (pinfunction "TP_TP") (pintype "input"))
    )
    (net (code "57") (name "Net-(IC1B--IN)") (class "Default")
      (node (ref "IC1") (pin "6") (pinfunction "-IN_6") (pintype "input"))
      (node (ref "R14") (pin "1") (pinfunction "1_1") (pintype "passive"))
      (node (ref "R17") (pin "1") (pinfunction "1_1") (pintype "passive"))
    )
    (net (code "58") (name "Net-(IC1B-OUT)") (class "Default")
      (node (ref "IC1") (pin "7") (pinfunction "OUT_7") (pintype "output"))
      (node (ref "R12") (pin "2") (pinfunction "2_2") (pintype "passive"))
      (node (ref "R17") (pin "2") (pinfunction "2_2") (pintype "passive"))
    )
    (net (code "59") (name "Net-(IC2A-VOUT)") (class "Default")
      (node (ref "C1") (pin "1") (pinfunction "1_1") (pintype "passive"))
      (node (ref "IC2") (pin "1") (pinfunction "VOUT_1") (pintype "output"))
      (node (ref "L5") (pin "1") (pinfunction "1_1") (pintype "passive"))
    )
    (net (code "60") (name "Net-(IC4A-+IN)") (class "Default")
      (node (ref "IC4") (pin "3") (pinfunction "+IN_3") (pintype "input"))
      (node (ref "R27") (pin "2") (pinfunction "2_2") (pintype "passive"))
      (node (ref "R30") (pin "1") (pinfunction "1_1") (pintype "passive"))
    )
    (net (code "61") (name "Net-(IC4A-OUT)") (class "Default")
      (node (ref "C19") (pin "1") (pinfunction "1_1") (pintype "passive"))
      (node (ref "IC4") (pin "1") (pinfunction "OUT_1") (pintype "output"))
      (node (ref "L6") (pin "1") (pinfunction "1_1") (pintype "passive"))
      (node (ref "R27") (pin "1") (pinfunction "1_1") (pintype "passive"))
    )
    (net (code "62") (name "Net-(IC4B-+IN)") (class "Default")
      (node (ref "IC4") (pin "5") (pinfunction "+IN_5") (pintype "input"))
      (node (ref "R34") (pin "1") (pinfunction "1_1") (pintype "passive"))
      (node (ref "R35") (pin "2") (pinfunction "2_2") (pintype "passive"))
    )
    (net (code "63") (name "Net-(IC4B--IN)") (class "Default")
      (node (ref "IC4") (pin "6") (pinfunction "-IN_6") (pintype "input"))
      (node (ref "IC4") (pin "7") (pinfunction "OUT_7") (pintype "output"))
      (node (ref "R30") (pin "2") (pinfunction "2_2") (pintype "passive"))
      (node (ref "R31") (pin "2") (pinfunction "2_2") (pintype "passive"))
    )
    (net (code "64") (name "Net-(IC6A-+IN)") (class "Default")
      (node (ref "IC6") (pin "3") (pinfunction "+IN_3") (pintype "input"))
      (node (ref "R65") (pin "2") (pinfunction "2_2") (pintype "passive"))
      (node (ref "R66") (pin "2") (pinfunction "2_2") (pintype "passive"))
      (node (ref "TP5") (pin "TP") (pinfunction "TP_TP") (pintype "input"))
    )
    (net (code "65") (name "Net-(IC6A--IN)") (class "Default")
      (node (ref "IC6") (pin "2") (pinfunction "-IN_2") (pintype "input"))
      (node (ref "R10") (pin "1") (pinfunction "1_1") (pintype "passive"))
      (node (ref "R9") (pin "1") (pinfunction "1_1") (pintype "passive"))
    )
    (net (code "66") (name "Net-(IC6A-OUT)") (class "Default")
      (node (ref "IC6") (pin "1") (pinfunction "OUT_1") (pintype "output"))
      (node (ref "R10") (pin "2") (pinfunction "2_2") (pintype "passive"))
      (node (ref "R4") (pin "2") (pinfunction "2_2") (pintype "passive"))
    )
    (net (code "67") (name "Net-(IC6B-+IN)") (class "Default")
      (node (ref "IC6") (pin "5") (pinfunction "+IN_5") (pintype "input"))
      (node (ref "R67") (pin "1") (pinfunction "1_1") (pintype "passive"))
      (node (ref "R68") (pin "2") (pinfunction "2_2") (pintype "passive"))
      (node (ref "TP6") (pin "TP") (pinfunction "TP_TP") (pintype "input"))
    )
    (net (code "68") (name "Net-(IC6B--IN)") (class "Default")
      (node (ref "IC6") (pin "6") (pinfunction "-IN_6") (pintype "input"))
      (node (ref "R11") (pin "1") (pinfunction "1_1") (pintype "passive"))
      (node (ref "R8") (pin "1") (pinfunction "1_1") (pintype "passive"))
    )
    (net (code "69") (name "Net-(IC6B-OUT)") (class "Default")
      (node (ref "IC6") (pin "7") (pinfunction "OUT_7") (pintype "output"))
      (node (ref "R11") (pin "2") (pinfunction "2_2") (pintype "passive"))
      (node (ref "R6") (pin "2") (pinfunction "2_2") (pintype "passive"))
    )
    (net (code "70") (name "Net-(IC7A-+IN)") (class "Default")
      (node (ref "IC7") (pin "3") (pinfunction "+IN_3") (pintype "input"))
      (node (ref "R36") (pin "2") (pinfunction "2_2") (pintype "passive"))
      (node (ref "R37") (pin "1") (pinfunction "1_1") (pintype "passive"))
    )
    (net (code "71") (name "Net-(IC7A-OUT)") (class "Default")
      (node (ref "C20") (pin "1") (pinfunction "1_1") (pintype "passive"))
      (node (ref "IC7") (pin "1") (pinfunction "OUT_1") (pintype "output"))
      (node (ref "L7") (pin "1") (pinfunction "1_1") (pintype "passive"))
      (node (ref "R36") (pin "1") (pinfunction "1_1") (pintype "passive"))
    )
    (net (code "72") (name "Net-(IC7B-+IN)") (class "Default")
      (node (ref "IC7") (pin "5") (pinfunction "+IN_5") (pintype "input"))
      (node (ref "R39") (pin "1") (pinfunction "1_1") (pintype "passive"))
      (node (ref "R45") (pin "2") (pinfunction "2_2") (pintype "passive"))
    )
    (net (code "73") (name "Net-(IC7B--IN)") (class "Default")
      (node (ref "IC7") (pin "6") (pinfunction "-IN_6") (pintype "input"))
      (node (ref "IC7") (pin "7") (pinfunction "OUT_7") (pintype "output"))
      (node (ref "R37") (pin "2") (pinfunction "2_2") (pintype "passive"))
      (node (ref "R38") (pin "2") (pinfunction "2_2") (pintype "passive"))
    )
    (net (code "74") (name "Net-(IC10-A0)") (class "Default")
      (node (ref "IC10") (pin "1") (pinfunction "A0_1") (pintype "input"))
      (node (ref "R57") (pin "2") (pinfunction "2_2") (pintype "passive"))
    )
    (net (code "75") (name "Net-(IC10-A1)") (class "Default")
      (node (ref "IC10") (pin "2") (pinfunction "A1_2") (pintype "input"))
      (node (ref "R58") (pin "2") (pinfunction "2_2") (pintype "passive"))
    )
    (net (code "76") (name "Net-(IC10-A2)") (class "Default")
      (node (ref "IC10") (pin "3") (pinfunction "A2_3") (pintype "input"))
      (node (ref "R59") (pin "2") (pinfunction "2_2") (pintype "passive"))
    )
    (net (code "77") (name "Net-(IC10-SCL)") (class "Default")
      (node (ref "IC10") (pin "6") (pinfunction "SCL_6") (pintype "bidirectional"))
      (node (ref "R60") (pin "2") (pinfunction "2_2") (pintype "passive"))
      (node (ref "R64") (pin "1") (pinfunction "1_1") (pintype "passive"))
    )
    (net (code "78") (name "Net-(IC10-SDA)") (class "Default")
      (node (ref "IC10") (pin "5") (pinfunction "SDA_5") (pintype "bidirectional"))
      (node (ref "R61") (pin "2") (pinfunction "2_2") (pintype "passive"))
      (node (ref "R63") (pin "1") (pinfunction "1_1") (pintype "passive"))
    )
    (net (code "79") (name "Net-(IC10-WP)") (class "Default")
      (node (ref "IC10") (pin "7") (pinfunction "WP_7") (pintype "input"))
      (node (ref "R62") (pin "2") (pinfunction "2_2") (pintype "passive"))
    )
    (net (code "80") (name "Net-(J2-Pad2)") (class "Default")
      (node (ref "J2") (pin "2") (pinfunction "2_2") (pintype "passive"))
      (node (ref "R1") (pin "2") (pinfunction "2_2") (pintype "passive"))
    )
    (net (code "81") (name "Net-(J2-Pad3)") (class "Default")
      (node (ref "J2") (pin "3") (pinfunction "3_3") (pintype "passive"))
      (node (ref "R54") (pin "2") (pinfunction "2_2") (pintype "passive"))
    )
    (net (code "82") (name "Net-(J2-Pad4)") (class "Default")
      (node (ref "J2") (pin "4") (pinfunction "4_4") (pintype "passive"))
      (node (ref "R55") (pin "2") (pinfunction "2_2") (pintype "passive"))
    )
    (net (code "83") (name "Net-(J9-2)") (class "Default")
      (node (ref "J9") (pin "5") (pinfunction "2_5") (pintype "passive"))
      (node (ref "OK4") (pin "2") (pinfunction "C_2") (pintype "passive"))
    )
    (net (code "84") (name "Net-(J9-3)") (class "Default")
      (node (ref "J9") (pin "4") (pinfunction "3_4") (pintype "passive"))
      (node (ref "OK3") (pin "2") (pinfunction "C_2") (pintype "passive"))
    )
    (net (code "85") (name "Net-(J9-4)") (class "Default")
      (node (ref "J9") (pin "3") (pinfunction "4_3") (pintype "passive"))
      (node (ref "OK2") (pin "2") (pinfunction "C_2") (pintype "passive"))
    )
    (net (code "86") (name "Net-(J9-5)") (class "Default")
      (node (ref "J9") (pin "2") (pinfunction "5_2") (pintype "passive"))
      (node (ref "OK1") (pin "2") (pinfunction "C_2") (pintype "passive"))
    )
    (net (code "87") (name "Net-(L1-Pad2)") (class "Default")
      (node (ref "L1") (pin "2") (pinfunction "2_2") (pintype "passive"))
      (node (ref "R65") (pin "1") (pinfunction "1_1") (pintype "passive"))
    )
    (net (code "88") (name "Net-(L2-Pad2)") (class "Default")
      (node (ref "L2") (pin "2") (pinfunction "2_2") (pintype "passive"))
      (node (ref "R67") (pin "2") (pinfunction "2_2") (pintype "passive"))
    )
    (net (code "89") (name "Net-(L3-Pad2)") (class "Default")
      (node (ref "L3") (pin "2") (pinfunction "2_2") (pintype "passive"))
      (node (ref "R18") (pin "1") (pinfunction "1_1") (pintype "passive"))
    )
    (net (code "90") (name "Net-(L4-Pad2)") (class "Default")
      (node (ref "L4") (pin "2") (pinfunction "2_2") (pintype "passive"))
      (node (ref "R20") (pin "2") (pinfunction "2_2") (pintype "passive"))
    )
    (net (code "91") (name "Net-(OK1-A)") (class "Default")
      (node (ref "OK1") (pin "1") (pinfunction "A_1") (pintype "passive"))
      (node (ref "R40") (pin "1") (pinfunction "1_1") (pintype "passive"))
    )
    (net (code "92") (name "Net-(OK2-A)") (class "Default")
      (node (ref "OK2") (pin "1") (pinfunction "A_1") (pintype "passive"))
      (node (ref "R41") (pin "1") (pinfunction "1_1") (pintype "passive"))
    )
    (net (code "93") (name "Net-(OK3-A)") (class "Default")
      (node (ref "OK3") (pin "1") (pinfunction "A_1") (pintype "passive"))
      (node (ref "R42") (pin "1") (pinfunction "1_1") (pintype "passive"))
    )
    (net (code "94") (name "Net-(OK4-A)") (class "Default")
      (node (ref "OK4") (pin "1") (pinfunction "A_1") (pintype "passive"))
      (node (ref "R43") (pin "1") (pinfunction "1_1") (pintype "passive"))
    )
    (net (code "95") (name "Net-(OK5-A)") (class "Default")
      (node (ref "OK5") (pin "1") (pinfunction "A_1") (pintype "passive"))
      (node (ref "R44") (pin "1") (pinfunction "1_1") (pintype "passive"))
    )
    (net (code "96") (name "Net-(OK5-C)") (class "Default")
      (node (ref "J10") (pin "3") (pinfunction "3_3") (pintype "passive"))
      (node (ref "OK5") (pin "2") (pinfunction "C_2") (pintype "passive"))
    )
    (net (code "97") (name "Net-(OK6-A)") (class "Default")
      (node (ref "OK6") (pin "1") (pinfunction "A_1") (pintype "passive"))
      (node (ref "R32") (pin "2") (pinfunction "2_2") (pintype "passive"))
    )
    (net (code "98") (name "Net-(OK6-COL)") (class "Default")
      (node (ref "D11") (pin "C") (pinfunction "C_C") (pintype "passive"))
      (node (ref "OK6") (pin "4") (pinfunction "COL_4") (pintype "passive"))
      (node (ref "OK8") (pin "4") (pinfunction "COL_4") (pintype "passive"))
    )
    (net (code "99") (name "Net-(OK7-A)") (class "Default")
      (node (ref "OK7") (pin "1") (pinfunction "A_1") (pintype "passive"))
      (node (ref "R46") (pin "2") (pinfunction "2_2") (pintype "passive"))
    )
    (net (code "100") (name "Net-(OK7-COL)") (class "Default")
      (node (ref "J10") (pin "2") (pinfunction "2_2") (pintype "passive"))
      (node (ref "OK7") (pin "4") (pinfunction "COL_4") (pintype "passive"))
    )
    (net (code "101") (name "Net-(OK8-A)") (class "Default")
      (node (ref "OK8") (pin "1") (pinfunction "A_1") (pintype "passive"))
      (node (ref "R33") (pin "2") (pinfunction "2_2") (pintype "passive"))
    )
    (net (code "102") (name "Net-(OK9-A)") (class "Default")
      (node (ref "OK9") (pin "1") (pinfunction "A_1") (pintype "passive"))
      (node (ref "R48") (pin "2") (pinfunction "2_2") (pintype "passive"))
    )
    (net (code "103") (name "Net-(OK9-EMIT)") (class "Default")
      (node (ref "OK9") (pin "3") (pinfunction "EMIT_3") (pintype "passive"))
      (node (ref "R50") (pin "1") (pinfunction "1_1") (pintype "passive"))
    )
    (net (code "104") (name "Net-(OK10-A)") (class "Default")
      (node (ref "OK10") (pin "1") (pinfunction "A_1") (pintype "passive"))
      (node (ref "R23") (pin "2") (pinfunction "2_2") (pintype "passive"))
    )
    (net (code "105") (name "Net-(OK11-A)") (class "Default")
      (node (ref "OK11") (pin "1") (pinfunction "A_1") (pintype "passive"))
      (node (ref "R55") (pin "1") (pinfunction "1_1") (pintype "passive"))
    )
    (net (code "106") (name "Net-(OK12-A)") (class "Default")
      (node (ref "OK12") (pin "1") (pinfunction "A_1") (pintype "passive"))
      (node (ref "R54") (pin "1") (pinfunction "1_1") (pintype "passive"))
    )
    (net (code "107") (name "Net-(OK13-A)") (class "Default")
      (node (ref "OK13") (pin "1") (pinfunction "A_1") (pintype "passive"))
      (node (ref "R1") (pin "1") (pinfunction "1_1") (pintype "passive"))
    )
    (net (code "108") (name "Net-(OK14-C)") (class "Default")
      (node (ref "OK14") (pin "2") (pinfunction "C_2") (pintype "passive"))
      (node (ref "OK17") (pin "1") (pinfunction "A_1") (pintype "passive"))
      (node (ref "R29") (pin "2") (pinfunction "2_2") (pintype "passive"))
    )
    (net (code "109") (name "Net-(OK15-C)") (class "Default")
      (node (ref "OK15") (pin "2") (pinfunction "C_2") (pintype "passive"))
      (node (ref "OK18") (pin "1") (pinfunction "A_1") (pintype "passive"))
      (node (ref "R22") (pin "1") (pinfunction "1_1") (pintype "passive"))
    )
    (net (code "110") (name "Net-(OK19-A)") (class "Default")
      (node (ref "OK19") (pin "1") (pinfunction "A_1") (pintype "passive"))
      (node (ref "R26") (pin "2") (pinfunction "2_2") (pintype "passive"))
    )
    (net (code "111") (name "Net-(OK20-A)") (class "Default")
      (node (ref "OK20") (pin "1") (pinfunction "A_1") (pintype "passive"))
      (node (ref "R56") (pin "2") (pinfunction "2_2") (pintype "passive"))
    )
    (net (code "112") (name "Net-(PCB1-+5V.)") (class "Default")
      (node (ref "PCB1") (pin "5V.") (pinfunction "+5V._5V.") (pintype "bidirectional"))
      (node (ref "PCB1") (pin "5V..") (pinfunction "+5V.._5V..") (pintype "bidirectional"))
    )
    (net (code "113") (name "Net-(PCB1-14(TX3))") (class "Default")
      (node (ref "J8") (pin "9") (pinfunction "9_9") (pintype "passive"))
      (node (ref "PCB1") (pin "14") (pinfunction "14(TX3)_14") (pintype "bidirectional"))
    )
    (net (code "114") (name "Net-(PCB1-15(RX3))") (class "Default")
      (node (ref "J8") (pin "8") (pinfunction "8_8") (pintype "passive"))
      (node (ref "PCB1") (pin "15") (pinfunction "15(RX3)_15") (pintype "bidirectional"))
    )
    (net (code "115") (name "Net-(PCB1-16(TX2))") (class "Default")
      (node (ref "J8") (pin "7") (pinfunction "7_7") (pintype "passive"))
      (node (ref "PCB1") (pin "16") (pinfunction "16(TX2)_16") (pintype "bidirectional"))
    )
    (net (code "116") (name "Net-(PCB1-17(RX2))") (class "Default")
      (node (ref "J8") (pin "6") (pinfunction "6_6") (pintype "passive"))
      (node (ref "PCB1") (pin "17") (pinfunction "17(RX2)_17") (pintype "bidirectional"))
    )
    (net (code "117") (name "Net-(PCB1-18(TX1))") (class "Default")
      (node (ref "J8") (pin "5") (pinfunction "5_5") (pintype "passive"))
      (node (ref "PCB1") (pin "18") (pinfunction "18(TX1)_18") (pintype "bidirectional"))
    )
    (net (code "118") (name "Net-(PCB1-19(RX1))") (class "Default")
      (node (ref "J8") (pin "4") (pinfunction "4_4") (pintype "passive"))
      (node (ref "PCB1") (pin "19") (pinfunction "19(RX1)_19") (pintype "bidirectional"))
    )
    (net (code "119") (name "Net-(PCB1-20(SDA))") (class "Default")
      (node (ref "J8") (pin "3") (pinfunction "3_3") (pintype "passive"))
      (node (ref "PCB1") (pin "20") (pinfunction "20(SDA)_20") (pintype "bidirectional"))
    )
    (net (code "120") (name "Net-(PCB1-21(SCL))") (class "Default")
      (node (ref "J8") (pin "2") (pinfunction "2_2") (pintype "passive"))
      (node (ref "PCB1") (pin "21") (pinfunction "21(SCL)_21") (pintype "bidirectional"))
    )
    (net (code "121") (name "Net-(PCB1-IOREF)") (class "Default")
      (node (ref "PCB1") (pin "I/OREF") (pinfunction "IOREF_I/OREF") (pintype "bidirectional"))
      (node (ref "R24") (pin "1") (pinfunction "1_1") (pintype "passive"))
    )
    (net (code "122") (name "PRO") (class "Default")
      (node (ref "OK15") (pin "1") (pinfunction "A_1") (pintype "passive"))
      (node (ref "OK18") (pin "2") (pinfunction "C_2") (pintype "passive"))
      (node (ref "PCB1") (pin "42") (pinfunction "42_42") (pintype "bidirectional"))
    )
    (net (code "123") (name "PROL") (class "Default")
      (node (ref "J4") (pin "7") (pinfunction "7_7") (pintype "passive"))
      (node (ref "OK10") (pin "2") (pinfunction "C_2") (pintype "passive"))
    )
    (net (code "124") (name "PROL_MCU") (class "Default")
      (node (ref "OK10") (pin "4") (pinfunction "COL_4") (pintype "passive"))
      (node (ref "PCB1") (pin "13") (pinfunction "13_13") (pintype "bidirectional"))
    )
    (net (code "125") (name "PSON") (class "Default")
      (node (ref "PCB1") (pin "47") (pinfunction "47_47") (pintype "bidirectional"))
      (node (ref "R48") (pin "1") (pinfunction "1_1") (pintype "passive"))
    )
    (net (code "126") (name "PS_ON") (class "Default")
      (node (ref "J4") (pin "3") (pinfunction "3_3") (pintype "passive"))
      (node (ref "R50") (pin "2") (pinfunction "2_2") (pintype "passive"))
      (node (ref "R51") (pin "1") (pinfunction "1_1") (pintype "passive"))
    )
    (net (code "127") (name "REST") (class "Default")
      (node (ref "PCB1") (pin "41") (pinfunction "41_41") (pintype "bidirectional"))
      (node (ref "X1") (pin "33") (pinfunction "KL_33") (pintype "passive"))
    )
    (net (code "128") (name "RS") (class "Default")
      (node (ref "PCB1") (pin "38") (pinfunction "38_38") (pintype "bidirectional"))
      (node (ref "X1") (pin "7") (pinfunction "KL_7") (pintype "passive"))
    )
    (net (code "129") (name "RS_CS") (class "Default")
      (node (ref "PCB1") (pin "7") (pinfunction "7_7") (pintype "bidirectional"))
    )
    (net (code "130") (name "RXD") (class "Default")
      (node (ref "J7") (pin "1") (pinfunction "1_1") (pintype "passive"))
      (node (ref "PCB1") (pin "0") (pinfunction "0(RX)_0") (pintype "bidirectional"))
    )
    (net (code "131") (name "SCL") (class "Default")
      (node (ref "PCB1") (pin "SCL1") (pinfunction "SCL1_SCL1") (pintype "bidirectional"))
      (node (ref "R60") (pin "1") (pinfunction "1_1") (pintype "passive"))
    )
    (net (code "132") (name "SDA") (class "Default")
      (node (ref "PCB1") (pin "SDA1") (pinfunction "SDA1_SDA1") (pintype "bidirectional"))
      (node (ref "R61") (pin "1") (pinfunction "1_1") (pintype "passive"))
    )
    (net (code "133") (name "SD_CLK") (class "Default")
      (node (ref "PCB1") (pin "52") (pinfunction "52_52") (pintype "bidirectional"))
      (node (ref "X1") (pin "32") (pinfunction "KL_32") (pintype "passive"))
    )
    (net (code "134") (name "SD_CS") (class "Default")
      (node (ref "PCB1") (pin "53") (pinfunction "53_53") (pintype "bidirectional"))
      (node (ref "X1") (pin "36") (pinfunction "KL_36") (pintype "passive"))
    )
    (net (code "135") (name "SD_DIN") (class "Default")
      (node (ref "PCB1") (pin "51") (pinfunction "51_51") (pintype "bidirectional"))
      (node (ref "X1") (pin "34") (pinfunction "KL_34") (pintype "passive"))
    )
    (net (code "136") (name "SD_DO") (class "Default")
      (node (ref "PCB1") (pin "50") (pinfunction "50_50") (pintype "bidirectional"))
      (node (ref "X1") (pin "30") (pinfunction "KL_30") (pintype "passive"))
    )
    (net (code "137") (name "SWR") (class "Default")
      (node (ref "OK14") (pin "1") (pinfunction "A_1") (pintype "passive"))
      (node (ref "OK17") (pin "2") (pinfunction "C_2") (pintype "passive"))
      (node (ref "PCB1") (pin "A4") (pinfunction "A4_A4") (pintype "bidirectional"))
    )
    (net (code "138") (name "TEMP") (class "Default")
      (node (ref "PCB1") (pin "43") (pinfunction "43_43") (pintype "bidirectional"))
      (node (ref "R22") (pin "2") (pinfunction "2_2") (pintype "passive"))
    )
    (net (code "139") (name "TEMP_PRO") (class "Default")
      (node (ref "PCB1") (pin "A6") (pinfunction "A6_A6") (pintype "bidirectional"))
    )
    (net (code "140") (name "TUN") (class "Default")
      (node (ref "PCB1") (pin "A14") (pinfunction "CANRX_A14") (pintype "bidirectional"))
      (node (ref "R32") (pin "1") (pinfunction "1_1") (pintype "passive"))
    )
    (net (code "141") (name "TUNER") (class "Default")
      (node (ref "J4") (pin "2") (pinfunction "2_2") (pintype "passive"))
      (node (ref "OK6") (pin "3") (pinfunction "EMIT_3") (pintype "passive"))
      (node (ref "R47") (pin "1") (pinfunction "1_1") (pintype "passive"))
    )
    (net (code "142") (name "TXD") (class "Default")
      (node (ref "J7") (pin "3") (pinfunction "3_3") (pintype "passive"))
      (node (ref "PCB1") (pin "1") (pinfunction "1(TX)_1") (pintype "bidirectional"))
    )
    (net (code "143") (name "TXIN") (class "Default")
      (node (ref "OK5") (pin "4") (pinfunction "COL_4") (pintype "passive"))
      (node (ref "PCB1") (pin "44") (pinfunction "44_44") (pintype "bidirectional"))
    )
    (net (code "144") (name "TXL") (class "Default")
      (node (ref "J4") (pin "8") (pinfunction "8_8") (pintype "passive"))
      (node (ref "R56") (pin "1") (pinfunction "1_1") (pintype "passive"))
    )
    (net (code "145") (name "TXL_MCU") (class "Default")
      (node (ref "OK20") (pin "4") (pinfunction "COL_4") (pintype "passive"))
      (node (ref "PCB1") (pin "11") (pinfunction "11_11") (pintype "bidirectional"))
    )
    (net (code "146") (name "TXOUT") (class "Default")
      (node (ref "PCB1") (pin "45") (pinfunction "45_45") (pintype "bidirectional"))
      (node (ref "R46") (pin "1") (pinfunction "1_1") (pintype "passive"))
    )
    (net (code "147") (name "T_CLK") (class "Default")
      (node (ref "PCB1") (pin "6") (pinfunction "6_6") (pintype "bidirectional"))
      (node (ref "X1") (pin "18") (pinfunction "KL_18") (pintype "passive"))
    )
    (net (code "148") (name "T_CS") (class "Default")
      (node (ref "PCB1") (pin "5") (pinfunction "5_5") (pintype "bidirectional"))
      (node (ref "X1") (pin "20") (pinfunction "KL_20") (pintype "passive"))
    )
    (net (code "149") (name "T_DIN") (class "Default")
      (node (ref "PCB1") (pin "4") (pinfunction "4_4") (pintype "bidirectional"))
      (node (ref "X1") (pin "22") (pinfunction "KL_22") (pintype "passive"))
    )
    (net (code "150") (name "T_DO") (class "Default")
      (node (ref "PCB1") (pin "3") (pinfunction "3_3") (pintype "bidirectional"))
      (node (ref "X1") (pin "26") (pinfunction "KL_26") (pintype "passive"))
    )
    (net (code "151") (name "T_IRQ") (class "Default")
      (node (ref "PCB1") (pin "2") (pinfunction "2_2") (pintype "bidirectional"))
      (node (ref "X1") (pin "28") (pinfunction "KL_28") (pintype "passive"))
    )
    (net (code "152") (name "VC") (class "Default")
      (node (ref "PCB1") (pin "A5") (pinfunction "A5_A5") (pintype "bidirectional"))
      (node (ref "R29") (pin "1") (pinfunction "1_1") (pintype "passive"))
    )
    (net (code "153") (name "WAIT") (class "Default")
      (node (ref "J4") (pin "6") (pinfunction "6_6") (pintype "passive"))
      (node (ref "R26") (pin "1") (pinfunction "1_1") (pintype "passive"))
    )
    (net (code "154") (name "WAIT_MCU") (class "Default")
      (node (ref "OK19") (pin "4") (pinfunction "COL_4") (pintype "passive"))
      (node (ref "PCB1") (pin "12") (pinfunction "12_12") (pintype "bidirectional"))
    )
    (net (code "155") (name "WR") (class "Default")
      (node (ref "PCB1") (pin "39") (pinfunction "39_39") (pintype "bidirectional"))
      (node (ref "X1") (pin "9") (pinfunction "KL_9") (pintype "passive"))
    )
    (net (code "156") (name "unconnected-(PCB1-(N{slash}C)-PadN{slash}C)") (class "Default")
      (node (ref "PCB1") (pin "N/C") (pinfunction "(N/C)_N/C") (pintype "bidirectional"))
    )
    (net (code "157") (name "unconnected-(PCB1-Pad8)") (class "Default")
      (node (ref "PCB1") (pin "8") (pinfunction "8_8") (pintype "bidirectional"))
    )
    (net (code "158") (name "unconnected-(PCB1-Pad9)") (class "Default")
      (node (ref "PCB1") (pin "9") (pinfunction "9_9") (pintype "bidirectional"))
    )
    (net (code "159") (name "unconnected-(PCB1-Pad10)") (class "Default")
      (node (ref "PCB1") (pin "10") (pinfunction "10_10") (pintype "bidirectional"))
    )
    (net (code "160") (name "unconnected-(PCB1-PadGND)") (class "Default")
      (node (ref "PCB1") (pin "GND") (pinfunction "GND_GND") (pintype "bidirectional"))
    )
    (net (code "161") (name "unconnected-(PCB1-PadRESET)") (class "Default")
      (node (ref "PCB1") (pin "RESET") (pinfunction "RESET_RESET") (pintype "bidirectional"))
    )
    (net (code "162") (name "unconnected-(X1AF-KL-Pad38)") (class "Default")
      (node (ref "X1") (pin "38") (pinfunction "KL_38") (pintype "passive"))
    )
    (net (code "163") (name "unconnected-(X1AG-KL-Pad39)") (class "Default")
      (node (ref "X1") (pin "39") (pinfunction "KL_39") (pintype "passive"))
    )
    (net (code "164") (name "unconnected-(X1AI-KL-Pad40)") (class "Default")
      (node (ref "X1") (pin "40") (pinfunction "KL_40") (pintype "passive"))
    )
    (net (code "165") (name "unconnected-(X1AJ-KL-Pad5)") (class "Default")
      (node (ref "X1") (pin "5") (pinfunction "KL_5") (pintype "passive"))
    )
    (net (code "166") (name "unconnected-(X1Q-KL-Pad24)") (class "Default")
      (node (ref "X1") (pin "24") (pinfunction "KL_24") (pintype "passive"))
    )
    (net (code "167") (name "unconnected-(X1Y-KL-Pad31)") (class "Default")
      (node (ref "X1") (pin "31") (pinfunction "KL_31") (pintype "passive"))
    )
  )
)
